# switching-led-driver-v2_0.net
KiCad netlist of a schematic drawn in EAGLE
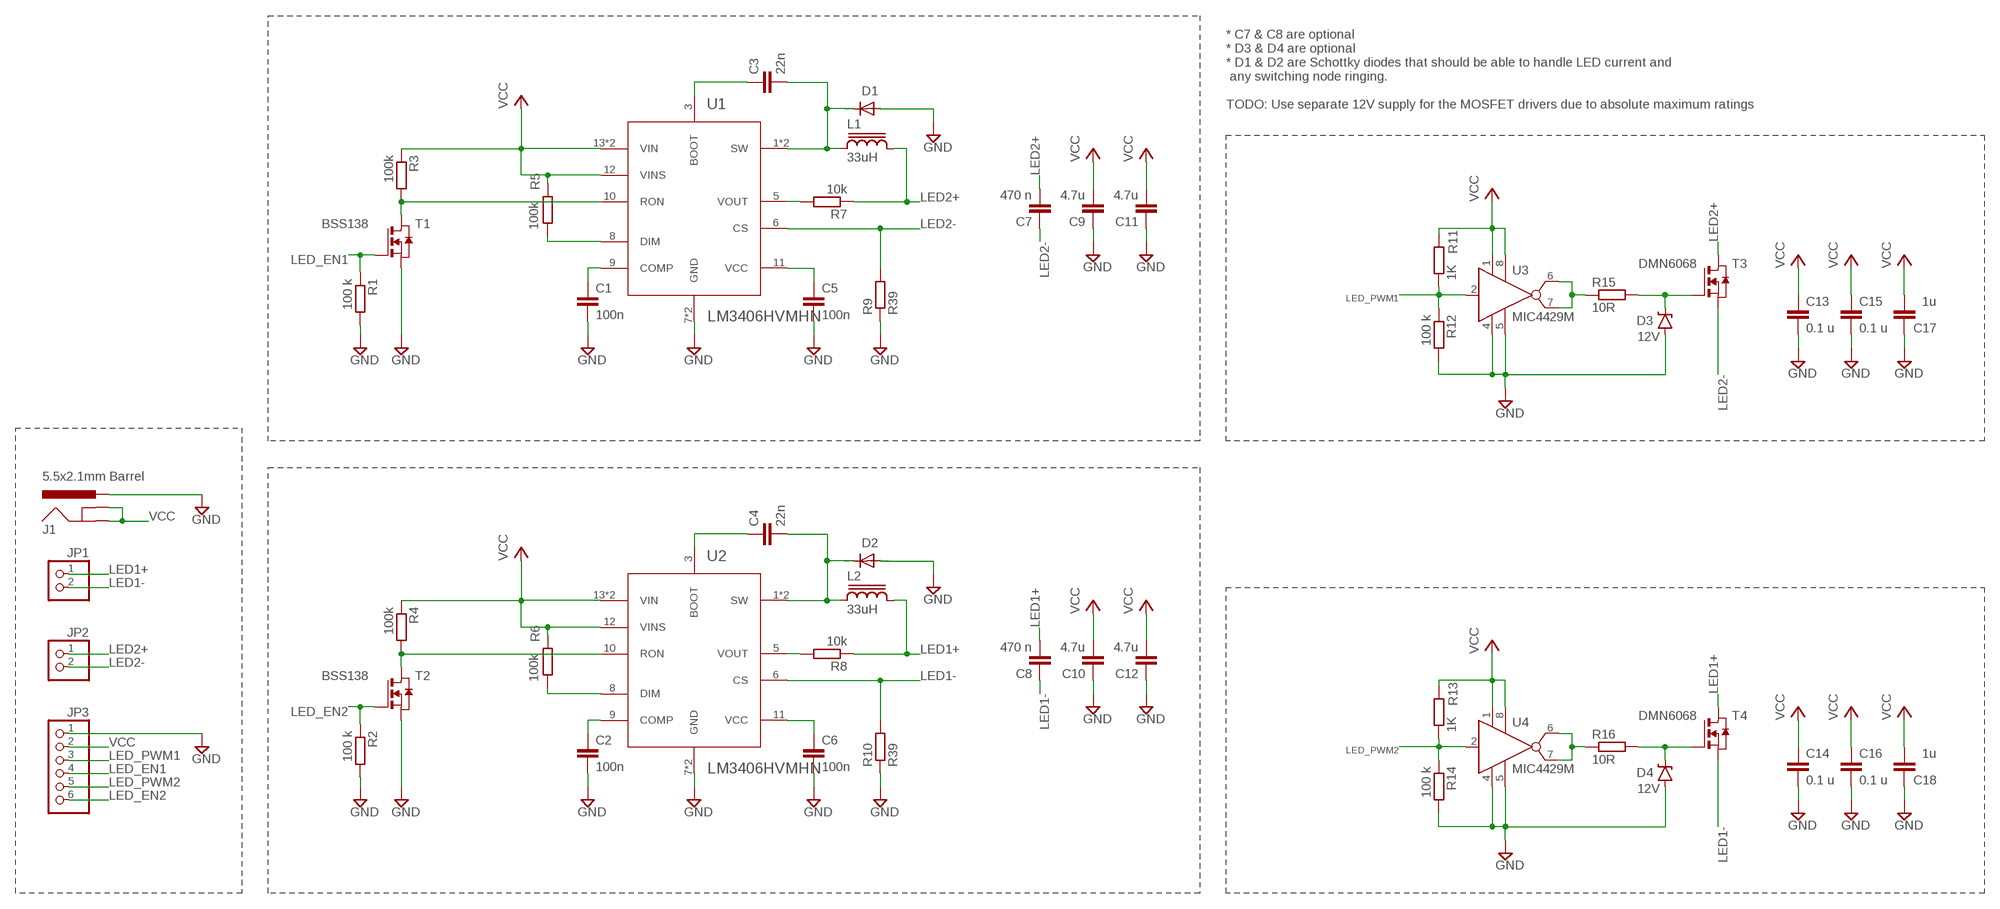
[diagram p0: schematic, sheet 1]

(export (version "E")
  (design (tool "Eeschema 10.0.6"))
  (components
    (comp (ref "C1")
      (value "100n")
      (footprint "eagle-import:C0805")
      (libsource (lib "eagle-import") (part "C-EUC0805"))
    )
    (comp (ref "C2")
      (value "100n")
      (footprint "eagle-import:C0805")
      (libsource (lib "eagle-import") (part "C-EUC0805"))
    )
    (comp (ref "C3")
      (value "22n")
      (footprint "eagle-import:C1206")
      (libsource (lib "eagle-import") (part "C-EUC1206"))
    )
    (comp (ref "C4")
      (value "22n")
      (footprint "eagle-import:C1206")
      (libsource (lib "eagle-import") (part "C-EUC1206"))
    )
    (comp (ref "C5")
      (value "100n")
      (footprint "eagle-import:C0805")
      (libsource (lib "eagle-import") (part "C-EUC0805"))
    )
    (comp (ref "C6")
      (value "100n")
      (footprint "eagle-import:C0805")
      (libsource (lib "eagle-import") (part "C-EUC0805"))
    )
    (comp (ref "C7")
      (value "470 n")
      (footprint "eagle-import:C1206")
      (libsource (lib "eagle-import") (part "C-EUC1206"))
    )
    (comp (ref "C8")
      (value "470 n")
      (footprint "eagle-import:C1206")
      (libsource (lib "eagle-import") (part "C-EUC1206"))
    )
    (comp (ref "C9")
      (value "4.7u")
      (footprint "eagle-import:C1210")
      (libsource (lib "eagle-import") (part "C-EUC1210"))
    )
    (comp (ref "C10")
      (value "4.7u")
      (footprint "eagle-import:C1210")
      (libsource (lib "eagle-import") (part "C-EUC1210"))
    )
    (comp (ref "C11")
      (value "4.7u")
      (footprint "eagle-import:C1210")
      (libsource (lib "eagle-import") (part "C-EUC1210"))
    )
    (comp (ref "C12")
      (value "4.7u")
      (footprint "eagle-import:C1210")
      (libsource (lib "eagle-import") (part "C-EUC1210"))
    )
    (comp (ref "C13")
      (value "0.1 u")
      (footprint "eagle-import:C0805")
      (libsource (lib "eagle-import") (part "C-EUC0805"))
    )
    (comp (ref "C14")
      (value "0.1 u")
      (footprint "eagle-import:C0805")
      (libsource (lib "eagle-import") (part "C-EUC0805"))
    )
    (comp (ref "C15")
      (value "0.1 u")
      (footprint "eagle-import:C0805")
      (libsource (lib "eagle-import") (part "C-EUC0805"))
    )
    (comp (ref "C16")
      (value "0.1 u")
      (footprint "eagle-import:C0805")
      (libsource (lib "eagle-import") (part "C-EUC0805"))
    )
    (comp (ref "C17")
      (value "1u")
      (footprint "eagle-import:C1210")
      (libsource (lib "eagle-import") (part "C-EUC1210"))
    )
    (comp (ref "C18")
      (value "1u")
      (footprint "eagle-import:C1210")
      (libsource (lib "eagle-import") (part "C-EUC1210"))
    )
    (comp (ref "D1")
      (value "12V")
      (footprint "eagle-import:DO-214AC")
      (libsource (lib "eagle-import") (part "DIODE-DO-214AC"))
    )
    (comp (ref "D2")
      (value "12V")
      (footprint "eagle-import:DO-214AC")
      (libsource (lib "eagle-import") (part "DIODE-DO-214AC"))
    )
    (comp (ref "D3")
      (value "12V")
      (footprint "eagle-import:SOD-123")
      (libsource (lib "eagle-import") (part "DIODE-ZENER16V"))
    )
    (comp (ref "D4")
      (value "12V")
      (footprint "eagle-import:SOD-123")
      (libsource (lib "eagle-import") (part "DIODE-ZENER16V"))
    )
    (comp (ref "J1")
      (value "5.5x2.1mm Barrel")
      (footprint "eagle-import:POWER_JACK_SMD")
      (libsource (lib "eagle-import") (part "POWER_JACKSMD"))
    )
    (comp (ref "JP1")
      (value "PINHD-1X2")
      (footprint "eagle-import:1X02")
      (libsource (lib "eagle-import") (part "PINHD-1X2"))
    )
    (comp (ref "JP2")
      (value "PINHD-1X2")
      (footprint "eagle-import:1X02")
      (libsource (lib "eagle-import") (part "PINHD-1X2"))
    )
    (comp (ref "JP3")
      (value "PINHD-1X6")
      (footprint "eagle-import:1X06")
      (libsource (lib "eagle-import") (part "PINHD-1X6"))
    )
    (comp (ref "L1")
      (value "33uH")
      (footprint "eagle-import:SRR1260")
      (libsource (lib "eagle-import") (part "SRR1260"))
    )
    (comp (ref "L2")
      (value "33uH")
      (footprint "eagle-import:SRR1260")
      (libsource (lib "eagle-import") (part "SRR1260"))
    )
    (comp (ref "R1")
      (value "100 k")
      (footprint "eagle-import:R0805")
      (libsource (lib "eagle-import") (part "R-EU_R0805"))
    )
    (comp (ref "R2")
      (value "100 k")
      (footprint "eagle-import:R0805")
      (libsource (lib "eagle-import") (part "R-EU_R0805"))
    )
    (comp (ref "R3")
      (value "100k")
      (footprint "eagle-import:R0805")
      (libsource (lib "eagle-import") (part "R-EU_R0805"))
    )
    (comp (ref "R4")
      (value "100k")
      (footprint "eagle-import:R0805")
      (libsource (lib "eagle-import") (part "R-EU_R0805"))
    )
    (comp (ref "R5")
      (value "100k")
      (footprint "eagle-import:R0805")
      (libsource (lib "eagle-import") (part "R-EU_R0805"))
    )
    (comp (ref "R6")
      (value "100k")
      (footprint "eagle-import:R0805")
      (libsource (lib "eagle-import") (part "R-EU_R0805"))
    )
    (comp (ref "R7")
      (value "10k")
      (footprint "eagle-import:R0805")
      (libsource (lib "eagle-import") (part "R-EU_R0805"))
    )
    (comp (ref "R8")
      (value "10k")
      (footprint "eagle-import:R0805")
      (libsource (lib "eagle-import") (part "R-EU_R0805"))
    )
    (comp (ref "R9")
      (value "R39")
      (footprint "eagle-import:R1206")
      (libsource (lib "eagle-import") (part "R-EU_R1206"))
    )
    (comp (ref "R10")
      (value "R39")
      (footprint "eagle-import:R1206")
      (libsource (lib "eagle-import") (part "R-EU_R1206"))
    )
    (comp (ref "R11")
      (value "1K")
      (footprint "eagle-import:R0805")
      (libsource (lib "eagle-import") (part "R-EU_R0805"))
    )
    (comp (ref "R12")
      (value "100 k")
      (footprint "eagle-import:R0805")
      (libsource (lib "eagle-import") (part "R-EU_R0805"))
    )
    (comp (ref "R13")
      (value "1K")
      (footprint "eagle-import:R0805")
      (libsource (lib "eagle-import") (part "R-EU_R0805"))
    )
    (comp (ref "R14")
      (value "100 k")
      (footprint "eagle-import:R0805")
      (libsource (lib "eagle-import") (part "R-EU_R0805"))
    )
    (comp (ref "R15")
      (value "10R")
      (footprint "eagle-import:R0805")
      (libsource (lib "eagle-import") (part "R-EU_R0805"))
    )
    (comp (ref "R16")
      (value "10R")
      (footprint "eagle-import:R0805")
      (libsource (lib "eagle-import") (part "R-EU_R0805"))
    )
    (comp (ref "T1")
      (value "BSS138")
      (footprint "eagle-import:SOT-23")
      (fields (field (name "OC_FARNELL") "2053833"))
      (libsource (lib "eagle-import") (part "NMOSSOT23"))
    )
    (comp (ref "T2")
      (value "BSS138")
      (footprint "eagle-import:SOT-23")
      (fields (field (name "OC_FARNELL") "2053833"))
      (libsource (lib "eagle-import") (part "NMOSSOT23"))
    )
    (comp (ref "T3")
      (value "DMN6068")
      (footprint "eagle-import:SOT223")
      (fields (field (name "OC_FARNELL") "2061415"))
      (libsource (lib "eagle-import") (part "NMOSSOT223"))
    )
    (comp (ref "T4")
      (value "DMN6068")
      (footprint "eagle-import:SOT223")
      (fields (field (name "OC_FARNELL") "2061415"))
      (libsource (lib "eagle-import") (part "NMOSSOT223"))
    )
    (comp (ref "U1")
      (value "LM3406HVMHN")
      (footprint "eagle-import:HTSSOP-14-NN")
      (libsource (lib "eagle-import") (part "LM3406HVMHN"))
    )
    (comp (ref "U2")
      (value "LM3406HVMHN")
      (footprint "eagle-import:HTSSOP-14-NN")
      (libsource (lib "eagle-import") (part "LM3406HVMHN"))
    )
    (comp (ref "U3")
      (value "MIC4429M")
      (footprint "eagle-import:SO08")
      (libsource (lib "eagle-import") (part "MIC4429M"))
    )
    (comp (ref "U4")
      (value "MIC4429M")
      (footprint "eagle-import:SO08")
      (libsource (lib "eagle-import") (part "MIC4429M"))
    )
  )
  (nets
    (net (code "1") (name "/LED1+") (class "Default")
      (node (ref "C8") (pin "2") (pinfunction "2_2") (pintype "passive"))
      (node (ref "JP1") (pin "1") (pinfunction "1_1") (pintype "passive"))
      (node (ref "L2") (pin "2") (pinfunction "2_2") (pintype "passive"))
      (node (ref "R8") (pin "1") (pinfunction "1_1") (pintype "passive"))
      (node (ref "T4") (pin "2") (pinfunction "D_2") (pintype "passive"))
      (node (ref "T4") (pin "4") (pinfunction "D_4") (pintype "passive"))
    )
    (net (code "2") (name "/LED1-") (class "Default")
      (node (ref "C8") (pin "1") (pinfunction "1_1") (pintype "passive"))
      (node (ref "JP1") (pin "2") (pinfunction "2_2") (pintype "passive"))
      (node (ref "R10") (pin "2") (pinfunction "2_2") (pintype "passive"))
      (node (ref "T4") (pin "3") (pinfunction "S_3") (pintype "passive"))
      (node (ref "U2") (pin "6") (pinfunction "CS_6") (pintype "input"))
    )
    (net (code "3") (name "/LED2+") (class "Default")
      (node (ref "C7") (pin "2") (pinfunction "2_2") (pintype "passive"))
      (node (ref "JP2") (pin "1") (pinfunction "1_1") (pintype "passive"))
      (node (ref "L1") (pin "2") (pinfunction "2_2") (pintype "passive"))
      (node (ref "R7") (pin "1") (pinfunction "1_1") (pintype "passive"))
      (node (ref "T3") (pin "2") (pinfunction "D_2") (pintype "passive"))
      (node (ref "T3") (pin "4") (pinfunction "D_4") (pintype "passive"))
    )
    (net (code "4") (name "/LED2-") (class "Default")
      (node (ref "C7") (pin "1") (pinfunction "1_1") (pintype "passive"))
      (node (ref "JP2") (pin "2") (pinfunction "2_2") (pintype "passive"))
      (node (ref "R9") (pin "2") (pinfunction "2_2") (pintype "passive"))
      (node (ref "T3") (pin "3") (pinfunction "S_3") (pintype "passive"))
      (node (ref "U1") (pin "6") (pinfunction "CS_6") (pintype "input"))
    )
    (net (code "5") (name "/LED_EN1") (class "Default")
      (node (ref "JP3") (pin "4") (pinfunction "4_4") (pintype "passive"))
      (node (ref "R1") (pin "1") (pinfunction "1_1") (pintype "passive"))
      (node (ref "T1") (pin "3") (pinfunction "G_3") (pintype "passive"))
    )
    (net (code "6") (name "/LED_EN2") (class "Default")
      (node (ref "JP3") (pin "6") (pinfunction "6_6") (pintype "passive"))
      (node (ref "R2") (pin "1") (pinfunction "1_1") (pintype "passive"))
      (node (ref "T2") (pin "3") (pinfunction "G_3") (pintype "passive"))
    )
    (net (code "7") (name "/LED_PWM1") (class "Default")
      (node (ref "JP3") (pin "3") (pinfunction "3_3") (pintype "passive"))
      (node (ref "R11") (pin "1") (pinfunction "1_1") (pintype "passive"))
      (node (ref "R12") (pin "1") (pinfunction "1_1") (pintype "passive"))
      (node (ref "U3") (pin "2") (pinfunction "IN_2") (pintype "input"))
    )
    (net (code "8") (name "/LED_PWM2") (class "Default")
      (node (ref "JP3") (pin "5") (pinfunction "5_5") (pintype "passive"))
      (node (ref "R13") (pin "1") (pinfunction "1_1") (pintype "passive"))
      (node (ref "R14") (pin "1") (pinfunction "1_1") (pintype "passive"))
      (node (ref "U4") (pin "2") (pinfunction "IN_2") (pintype "input"))
    )
    (net (code "9") (name "GND") (class "Default")
      (node (ref "C1") (pin "2") (pinfunction "2_2") (pintype "passive"))
      (node (ref "C10") (pin "1") (pinfunction "1_1") (pintype "passive"))
      (node (ref "C11") (pin "1") (pinfunction "1_1") (pintype "passive"))
      (node (ref "C12") (pin "1") (pinfunction "1_1") (pintype "passive"))
      (node (ref "C13") (pin "2") (pinfunction "2_2") (pintype "passive"))
      (node (ref "C14") (pin "2") (pinfunction "2_2") (pintype "passive"))
      (node (ref "C15") (pin "2") (pinfunction "2_2") (pintype "passive"))
      (node (ref "C16") (pin "2") (pinfunction "2_2") (pintype "passive"))
      (node (ref "C17") (pin "1") (pinfunction "1_1") (pintype "passive"))
      (node (ref "C18") (pin "1") (pinfunction "1_1") (pintype "passive"))
      (node (ref "C2") (pin "2") (pinfunction "2_2") (pintype "passive"))
      (node (ref "C5") (pin "2") (pinfunction "2_2") (pintype "passive"))
      (node (ref "C6") (pin "2") (pinfunction "2_2") (pintype "passive"))
      (node (ref "C9") (pin "1") (pinfunction "1_1") (pintype "passive"))
      (node (ref "D1") (pin "A") (pinfunction "A_A") (pintype "passive"))
      (node (ref "D2") (pin "A") (pinfunction "A_A") (pintype "passive"))
      (node (ref "D3") (pin "A") (pinfunction "A_A") (pintype "passive"))
      (node (ref "D4") (pin "A") (pinfunction "A_A") (pintype "passive"))
      (node (ref "J1") (pin "VIN0") (pinfunction "PWR_VIN0") (pintype "bidirectional"))
      (node (ref "JP3") (pin "1") (pinfunction "1_1") (pintype "passive"))
      (node (ref "R1") (pin "2") (pinfunction "2_2") (pintype "passive"))
      (node (ref "R10") (pin "1") (pinfunction "1_1") (pintype "passive"))
      (node (ref "R12") (pin "2") (pinfunction "2_2") (pintype "passive"))
      (node (ref "R14") (pin "2") (pinfunction "2_2") (pintype "passive"))
      (node (ref "R2") (pin "2") (pinfunction "2_2") (pintype "passive"))
      (node (ref "R9") (pin "1") (pinfunction "1_1") (pintype "passive"))
      (node (ref "T1") (pin "2") (pinfunction "S_2") (pintype "passive"))
      (node (ref "T2") (pin "2") (pinfunction "S_2") (pintype "passive"))
      (node (ref "U1") (pin "15") (pinfunction "GND_15") (pintype "passive"))
      (node (ref "U1") (pin "7") (pinfunction "GND_7") (pintype "passive"))
      (node (ref "U2") (pin "15") (pinfunction "GND_15") (pintype "passive"))
      (node (ref "U2") (pin "7") (pinfunction "GND_7") (pintype "passive"))
      (node (ref "U3") (pin "4") (pinfunction "GND1_4") (pintype "power_in"))
      (node (ref "U3") (pin "5") (pinfunction "GND2_5") (pintype "power_in"))
      (node (ref "U4") (pin "4") (pinfunction "GND1_4") (pintype "power_in"))
      (node (ref "U4") (pin "5") (pinfunction "GND2_5") (pintype "power_in"))
    )
    (net (code "10") (name "Net-(C3-Pad2)") (class "Default")
      (node (ref "C3") (pin "2") (pinfunction "2_2") (pintype "passive"))
      (node (ref "D1") (pin "C") (pinfunction "C_C") (pintype "passive"))
      (node (ref "L1") (pin "1") (pinfunction "1_1") (pintype "passive"))
      (node (ref "U1") (pin "1") (pinfunction "SW_1") (pintype "output"))
      (node (ref "U1") (pin "2") (pinfunction "SW_2") (pintype "output"))
    )
    (net (code "11") (name "Net-(C4-Pad2)") (class "Default")
      (node (ref "C4") (pin "2") (pinfunction "2_2") (pintype "passive"))
      (node (ref "D2") (pin "C") (pinfunction "C_C") (pintype "passive"))
      (node (ref "L2") (pin "1") (pinfunction "1_1") (pintype "passive"))
      (node (ref "U2") (pin "1") (pinfunction "SW_1") (pintype "output"))
      (node (ref "U2") (pin "2") (pinfunction "SW_2") (pintype "output"))
    )
    (net (code "12") (name "Net-(T1-D)") (class "Default")
      (node (ref "R3") (pin "2") (pinfunction "2_2") (pintype "passive"))
      (node (ref "T1") (pin "1") (pinfunction "D_1") (pintype "passive"))
      (node (ref "U1") (pin "10") (pinfunction "RON_10") (pintype "input"))
    )
    (net (code "13") (name "Net-(T2-D)") (class "Default")
      (node (ref "R4") (pin "2") (pinfunction "2_2") (pintype "passive"))
      (node (ref "T2") (pin "1") (pinfunction "D_1") (pintype "passive"))
      (node (ref "U2") (pin "10") (pinfunction "RON_10") (pintype "input"))
    )
    (net (code "14") (name "Net-(T3-G)") (class "Default")
      (node (ref "D3") (pin "C") (pinfunction "C_C") (pintype "passive"))
      (node (ref "R15") (pin "2") (pinfunction "2_2") (pintype "passive"))
      (node (ref "T3") (pin "1") (pinfunction "G_1") (pintype "passive"))
    )
    (net (code "15") (name "Net-(T4-G)") (class "Default")
      (node (ref "D4") (pin "C") (pinfunction "C_C") (pintype "passive"))
      (node (ref "R16") (pin "2") (pinfunction "2_2") (pintype "passive"))
      (node (ref "T4") (pin "1") (pinfunction "G_1") (pintype "passive"))
    )
    (net (code "16") (name "Net-(U1-BOOT)") (class "Default")
      (node (ref "C3") (pin "1") (pinfunction "1_1") (pintype "passive"))
      (node (ref "U1") (pin "3") (pinfunction "BOOT_3") (pintype "input"))
    )
    (net (code "17") (name "Net-(U1-COMP)") (class "Default")
      (node (ref "C1") (pin "1") (pinfunction "1_1") (pintype "passive"))
      (node (ref "U1") (pin "9") (pinfunction "COMP_9") (pintype "input"))
    )
    (net (code "18") (name "Net-(U1-DIM)") (class "Default")
      (node (ref "R5") (pin "1") (pinfunction "1_1") (pintype "passive"))
      (node (ref "U1") (pin "8") (pinfunction "DIM_8") (pintype "input"))
    )
    (net (code "19") (name "Net-(U1-VCC)") (class "Default")
      (node (ref "C5") (pin "1") (pinfunction "1_1") (pintype "passive"))
      (node (ref "U1") (pin "11") (pinfunction "VCC_11") (pintype "power_in"))
    )
    (net (code "20") (name "Net-(U1-VOUT)") (class "Default")
      (node (ref "R7") (pin "2") (pinfunction "2_2") (pintype "passive"))
      (node (ref "U1") (pin "5") (pinfunction "VOUT_5") (pintype "output"))
    )
    (net (code "21") (name "Net-(U2-BOOT)") (class "Default")
      (node (ref "C4") (pin "1") (pinfunction "1_1") (pintype "passive"))
      (node (ref "U2") (pin "3") (pinfunction "BOOT_3") (pintype "input"))
    )
    (net (code "22") (name "Net-(U2-COMP)") (class "Default")
      (node (ref "C2") (pin "1") (pinfunction "1_1") (pintype "passive"))
      (node (ref "U2") (pin "9") (pinfunction "COMP_9") (pintype "input"))
    )
    (net (code "23") (name "Net-(U2-DIM)") (class "Default")
      (node (ref "R6") (pin "1") (pinfunction "1_1") (pintype "passive"))
      (node (ref "U2") (pin "8") (pinfunction "DIM_8") (pintype "input"))
    )
    (net (code "24") (name "Net-(U2-VCC)") (class "Default")
      (node (ref "C6") (pin "1") (pinfunction "1_1") (pintype "passive"))
      (node (ref "U2") (pin "11") (pinfunction "VCC_11") (pintype "power_in"))
    )
    (net (code "25") (name "Net-(U2-VOUT)") (class "Default")
      (node (ref "R8") (pin "2") (pinfunction "2_2") (pintype "passive"))
      (node (ref "U2") (pin "5") (pinfunction "VOUT_5") (pintype "output"))
    )
    (net (code "26") (name "Net-(U3-OUT1)") (class "Default")
      (node (ref "R15") (pin "1") (pinfunction "1_1") (pintype "passive"))
      (node (ref "U3") (pin "6") (pinfunction "OUT1_6") (pintype "passive"))
      (node (ref "U3") (pin "7") (pinfunction "OUT2_7") (pintype "passive"))
    )
    (net (code "27") (name "Net-(U4-OUT1)") (class "Default")
      (node (ref "R16") (pin "1") (pinfunction "1_1") (pintype "passive"))
      (node (ref "U4") (pin "6") (pinfunction "OUT1_6") (pintype "passive"))
      (node (ref "U4") (pin "7") (pinfunction "OUT2_7") (pintype "passive"))
    )
    (net (code "28") (name "VCC") (class "Default")
      (node (ref "C10") (pin "2") (pinfunction "2_2") (pintype "passive"))
      (node (ref "C11") (pin "2") (pinfunction "2_2") (pintype "passive"))
      (node (ref "C12") (pin "2") (pinfunction "2_2") (pintype "passive"))
      (node (ref "C13") (pin "1") (pinfunction "1_1") (pintype "passive"))
      (node (ref "C14") (pin "1") (pinfunction "1_1") (pintype "passive"))
      (node (ref "C15") (pin "1") (pinfunction "1_1") (pintype "passive"))
      (node (ref "C16") (pin "1") (pinfunction "1_1") (pintype "passive"))
      (node (ref "C17") (pin "2") (pinfunction "2_2") (pintype "passive"))
      (node (ref "C18") (pin "2") (pinfunction "2_2") (pintype "passive"))
      (node (ref "C9") (pin "2") (pinfunction "2_2") (pintype "passive"))
      (node (ref "J1") (pin "GND") (pinfunction "GNDBREAK_GND") (pintype "bidirectional"))
      (node (ref "J1") (pin "P$4") (pinfunction "GND_P$4") (pintype "bidirectional"))
      (node (ref "JP3") (pin "2") (pinfunction "2_2") (pintype "passive"))
      (node (ref "R11") (pin "2") (pinfunction "2_2") (pintype "passive"))
      (node (ref "R13") (pin "2") (pinfunction "2_2") (pintype "passive"))
      (node (ref "R3") (pin "1") (pinfunction "1_1") (pintype "passive"))
      (node (ref "R4") (pin "1") (pinfunction "1_1") (pintype "passive"))
      (node (ref "R5") (pin "2") (pinfunction "2_2") (pintype "passive"))
      (node (ref "R6") (pin "2") (pinfunction "2_2") (pintype "passive"))
      (node (ref "U1") (pin "12") (pinfunction "VINS_12") (pintype "input"))
      (node (ref "U1") (pin "13") (pinfunction "VIN_13") (pintype "input"))
      (node (ref "U1") (pin "14") (pinfunction "VIN_14") (pintype "input"))
      (node (ref "U2") (pin "12") (pinfunction "VINS_12") (pintype "input"))
      (node (ref "U2") (pin "13") (pinfunction "VIN_13") (pintype "input"))
      (node (ref "U2") (pin "14") (pinfunction "VIN_14") (pintype "input"))
      (node (ref "U3") (pin "1") (pinfunction "VS1_1") (pintype "power_in"))
      (node (ref "U3") (pin "8") (pinfunction "VS2_8") (pintype "power_in"))
      (node (ref "U4") (pin "1") (pinfunction "VS1_1") (pintype "power_in"))
      (node (ref "U4") (pin "8") (pinfunction "VS2_8") (pintype "power_in"))
    )
  )
)
